# 04_ZYNQ_Config.net
KiCad netlist of a schematic drawn in Altium Designer
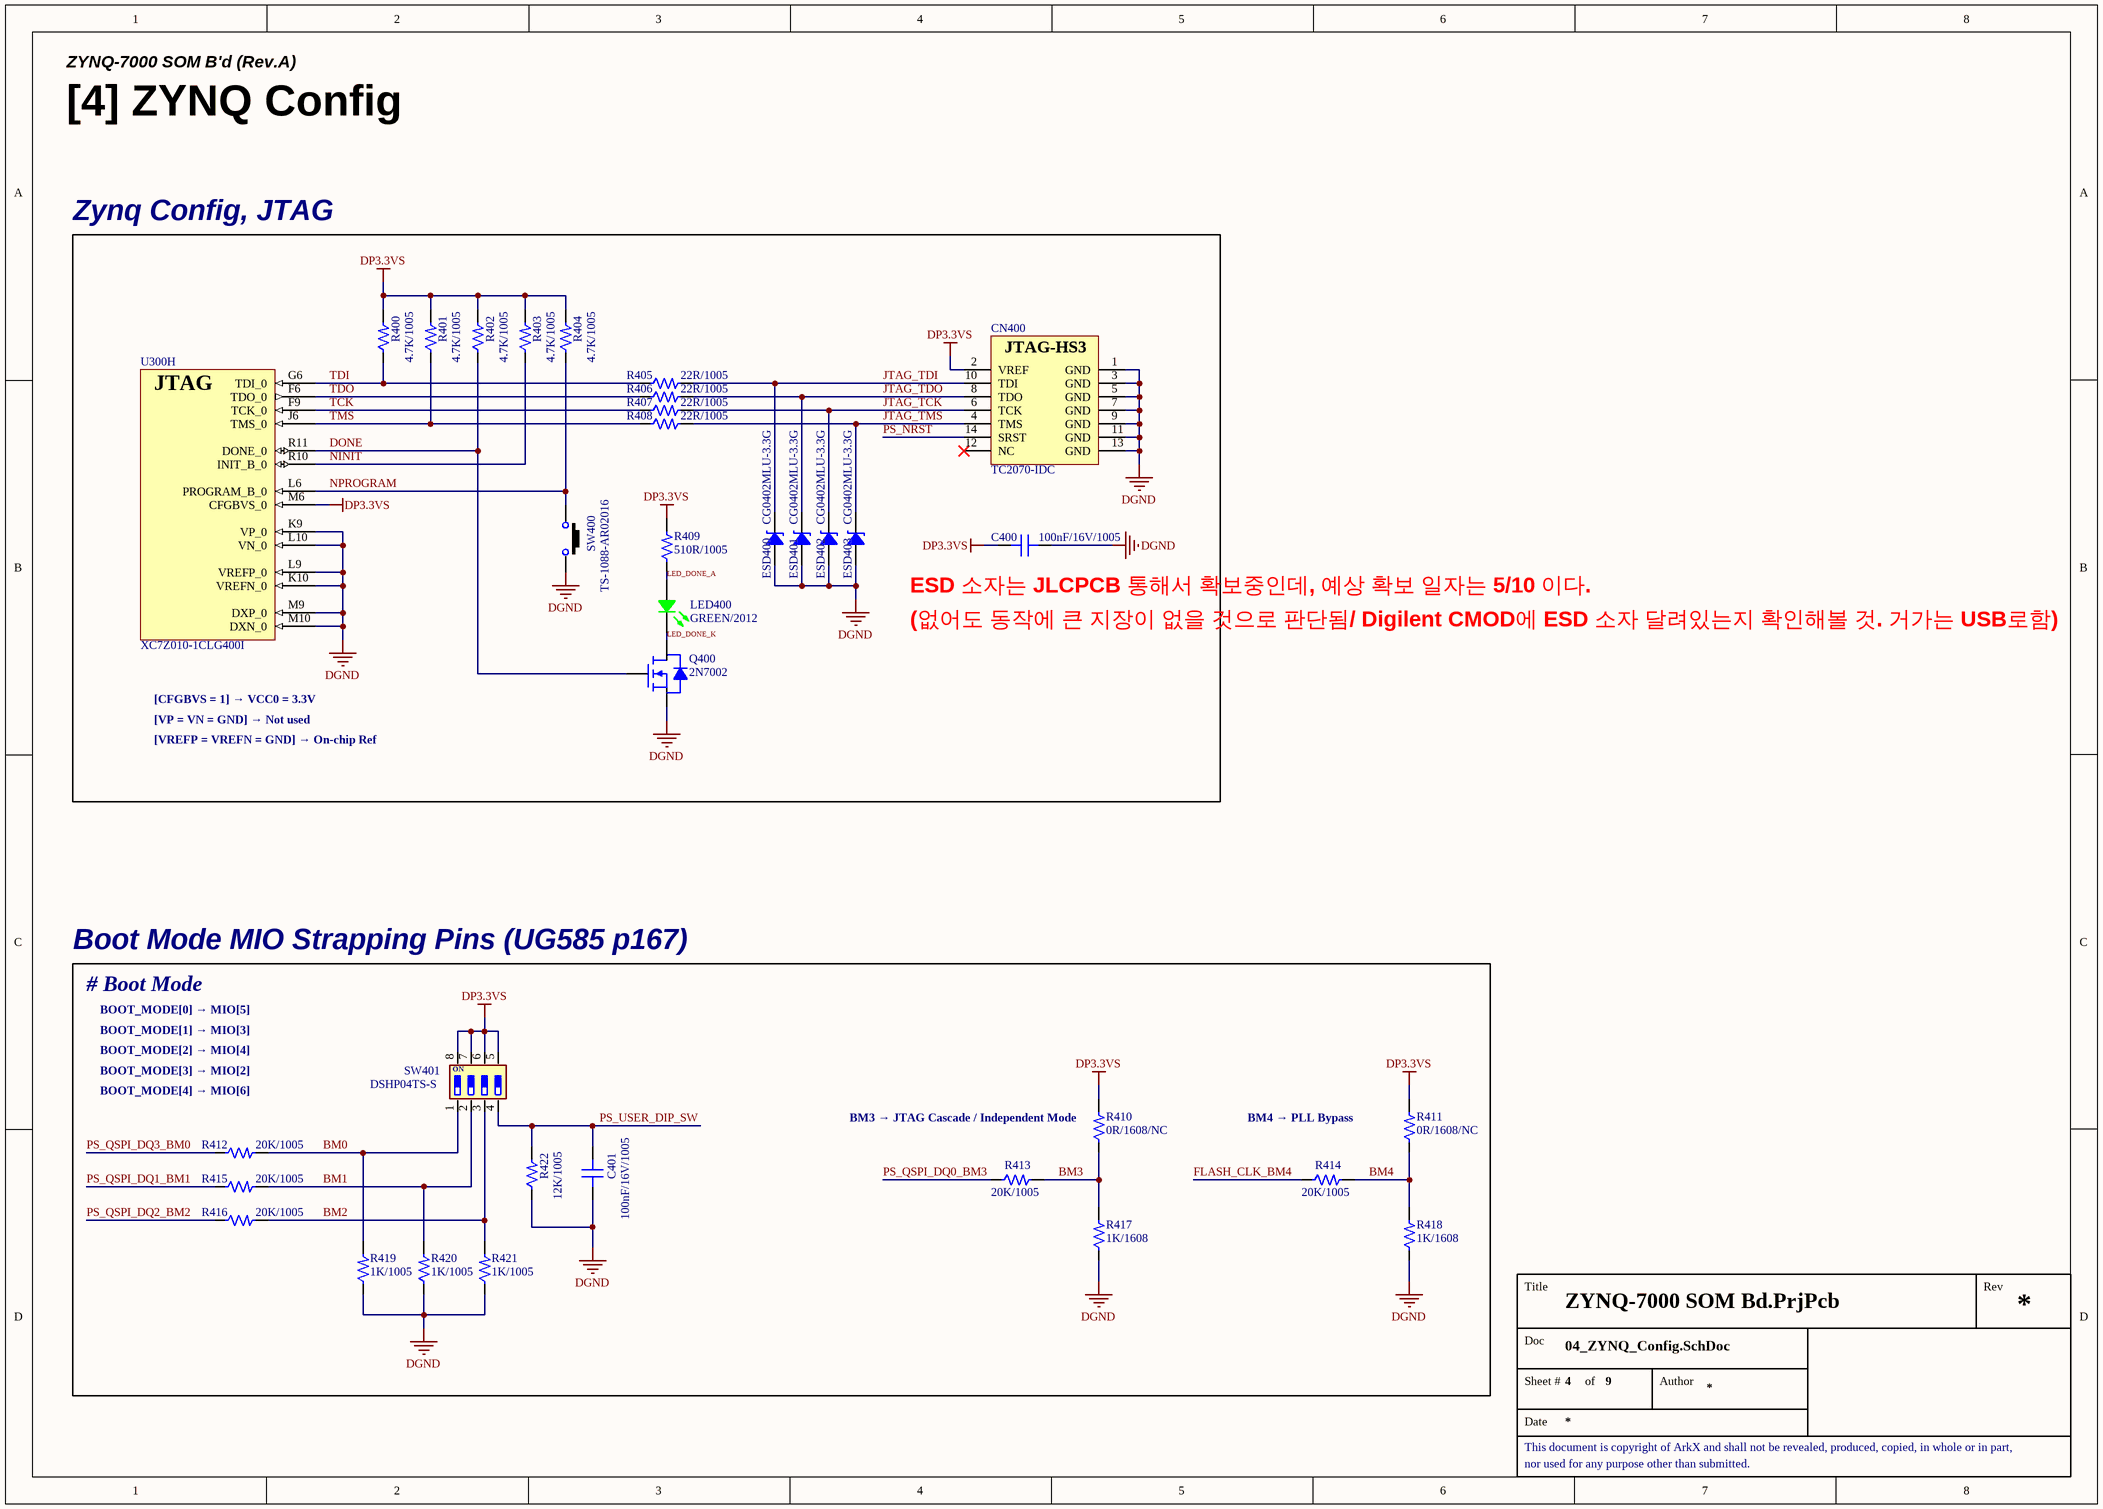
[diagram p0: 04_ZYNQ_Config.SchDoc]

(export (version "E")
  (design (tool "Eeschema 10.0.6"))
  (components
    (comp (ref "C400")
      (value "100nF/16V/1005")
      (footprint "CAP 1005 (0402_INCH)")
      (description "Ceramic CAP_100nF/16V/1005")
      (fields (field (name "LCSC PART #") "C1525"))
      (libsource (lib "Arkx") (part "CAP_100nF/16V/1005"))
    )
    (comp (ref "C401")
      (value "100nF/16V/1005")
      (footprint "CAP 1005 (0402_INCH)")
      (description "Ceramic CAP_100nF/16V/1005")
      (fields (field (name "LCSC PART #") "C1525"))
      (libsource (lib "Arkx") (part "CAP_100nF/16V/1005"))
    )
    (comp (ref "CN400")
      (value "TC2070-IDC")
      (footprint "CON_TC2070-IDC")
      (description "TC2070 14-pin Plug-of-Nails™ (with legs) to 14 pin 2mm female IDC connector.")
      (libsource (lib "Arkx") (part "CON_TC2070-IDC(JTAG-HS3)"))
    )
    (comp (ref "ESD400")
      (value "CG0402MLU-3.3G")
      (footprint "RES 1005 (0402_inch)")
      (description "Varistor 1 Circuit Surface Mount, MLCV 0402 (1005 Metric)")
      (fields (field (name "LCSC PART #") "C2655393"))
      (libsource (lib "Arkx") (part "ESD_CG0402MLU-3.3G"))
    )
    (comp (ref "ESD401")
      (value "CG0402MLU-3.3G")
      (footprint "RES 1005 (0402_inch)")
      (description "Varistor 1 Circuit Surface Mount, MLCV 0402 (1005 Metric)")
      (fields (field (name "LCSC PART #") "C2655393"))
      (libsource (lib "Arkx") (part "ESD_CG0402MLU-3.3G"))
    )
    (comp (ref "ESD402")
      (value "CG0402MLU-3.3G")
      (footprint "RES 1005 (0402_inch)")
      (description "Varistor 1 Circuit Surface Mount, MLCV 0402 (1005 Metric)")
      (fields (field (name "LCSC PART #") "C2655393"))
      (libsource (lib "Arkx") (part "ESD_CG0402MLU-3.3G"))
    )
    (comp (ref "ESD403")
      (value "CG0402MLU-3.3G")
      (footprint "RES 1005 (0402_inch)")
      (description "Varistor 1 Circuit Surface Mount, MLCV 0402 (1005 Metric)")
      (fields (field (name "LCSC PART #") "C2655393"))
      (libsource (lib "Arkx") (part "ESD_CG0402MLU-3.3G"))
    )
    (comp (ref "LED400")
      (value "GREEN/2012")
      (footprint "LED MHT170RGBCT (GREEN)")
      (fields (field (name "LCSC PART #") "C2962094"))
      (libsource (lib "Arkx") (part "LED_MHT170RGBCT(GREEN)"))
    )
    (comp (ref "Q400")
      (value "2N7002")
      (footprint "SOT 23-3 (DIODES INCORPORATED)")
      (description "60V 115mA 200mW 7.5Ω@10V,500mA N Channel SOT-23  MOSFETs ROHS")
      (fields (field (name "LCSC PART #") "C8545"))
      (libsource (lib "Arkx") (part "FET_2N7002"))
    )
    (comp (ref "R400")
      (value "4.7K/1005")
      (footprint "RES 1005 (0402_inch)")
      (description "RES_4.7K/1005/62.5mW")
      (fields (field (name "LCSC PART #") "C25900"))
      (libsource (lib "Arkx") (part "RES_4.7K/1005/62.5mW"))
    )
    (comp (ref "R401")
      (value "4.7K/1005")
      (footprint "RES 1005 (0402_inch)")
      (description "RES_4.7K/1005/62.5mW")
      (fields (field (name "LCSC PART #") "C25900"))
      (libsource (lib "Arkx") (part "RES_4.7K/1005/62.5mW"))
    )
    (comp (ref "R402")
      (value "4.7K/1005")
      (footprint "RES 1005 (0402_inch)")
      (description "RES_4.7K/1005/62.5mW")
      (fields (field (name "LCSC PART #") "C25900"))
      (libsource (lib "Arkx") (part "RES_4.7K/1005/62.5mW"))
    )
    (comp (ref "R403")
      (value "4.7K/1005")
      (footprint "RES 1005 (0402_inch)")
      (description "RES_4.7K/1005/62.5mW")
      (fields (field (name "LCSC PART #") "C25900"))
      (libsource (lib "Arkx") (part "RES_4.7K/1005/62.5mW"))
    )
    (comp (ref "R404")
      (value "4.7K/1005")
      (footprint "RES 1005 (0402_inch)")
      (description "RES_4.7K/1005/62.5mW")
      (fields (field (name "LCSC PART #") "C25900"))
      (libsource (lib "Arkx") (part "RES_4.7K/1005/62.5mW"))
    )
    (comp (ref "R405")
      (value "22R/1005")
      (footprint "RES 1005 (0402_inch)")
      (description "RES_22R/1005/62.5mW")
      (fields (field (name "LCSC PART #") "C25092"))
      (libsource (lib "Arkx") (part "RES_22R/1005/62.5mW"))
    )
    (comp (ref "R406")
      (value "22R/1005")
      (footprint "RES 1005 (0402_inch)")
      (description "RES_22R/1005/62.5mW")
      (fields (field (name "LCSC PART #") "C25092"))
      (libsource (lib "Arkx") (part "RES_22R/1005/62.5mW"))
    )
    (comp (ref "R407")
      (value "22R/1005")
      (footprint "RES 1005 (0402_inch)")
      (description "RES_22R/1005/62.5mW")
      (fields (field (name "LCSC PART #") "C25092"))
      (libsource (lib "Arkx") (part "RES_22R/1005/62.5mW"))
    )
    (comp (ref "R408")
      (value "22R/1005")
      (footprint "RES 1005 (0402_inch)")
      (description "RES_22R/1005/62.5mW")
      (fields (field (name "LCSC PART #") "C25092"))
      (libsource (lib "Arkx") (part "RES_22R/1005/62.5mW"))
    )
    (comp (ref "R409")
      (value "510R/1005")
      (footprint "RES 1005 (0402_inch)")
      (description "RES_510R/1005/62.5mW")
      (fields (field (name "LCSC PART #") "C25123"))
      (libsource (lib "Arkx") (part "RES_510R/1005/62.5mW"))
    )
    (comp (ref "R410")
      (value "0R/1608/NC")
      (footprint "RES 1608 (0603_inch)/NC")
      (description "0R/1608/0.1W/NC")
      (libsource (lib "Arkx") (part "RES_NC_0R/1608/0.1W"))
    )
    (comp (ref "R411")
      (value "0R/1608/NC")
      (footprint "RES 1608 (0603_inch)/NC")
      (description "0R/1608/0.1W/NC")
      (libsource (lib "Arkx") (part "RES_NC_0R/1608/0.1W"))
    )
    (comp (ref "R412")
      (value "20K/1005")
      (footprint "RES 1005 (0402_inch)")
      (description "RES_20K/1005/62.5mW")
      (fields (field (name "LCSC PART #") "C25765"))
      (libsource (lib "Arkx") (part "RES_20K/1005/62.5mW"))
    )
    (comp (ref "R413")
      (value "20K/1005")
      (footprint "RES 1005 (0402_inch)")
      (description "RES_20K/1005/62.5mW")
      (fields (field (name "LCSC PART #") "C25765"))
      (libsource (lib "Arkx") (part "RES_20K/1005/62.5mW"))
    )
    (comp (ref "R414")
      (value "20K/1005")
      (footprint "RES 1005 (0402_inch)")
      (description "RES_20K/1005/62.5mW")
      (fields (field (name "LCSC PART #") "C25765"))
      (libsource (lib "Arkx") (part "RES_20K/1005/62.5mW"))
    )
    (comp (ref "R415")
      (value "20K/1005")
      (footprint "RES 1005 (0402_inch)")
      (description "RES_20K/1005/62.5mW")
      (fields (field (name "LCSC PART #") "C25765"))
      (libsource (lib "Arkx") (part "RES_20K/1005/62.5mW"))
    )
    (comp (ref "R416")
      (value "20K/1005")
      (footprint "RES 1005 (0402_inch)")
      (description "RES_20K/1005/62.5mW")
      (fields (field (name "LCSC PART #") "C25765"))
      (libsource (lib "Arkx") (part "RES_20K/1005/62.5mW"))
    )
    (comp (ref "R417")
      (value "1K/1608")
      (footprint "RES 1608 (0603_inch)")
      (description "RES_1K/1608/0.1W")
      (fields (field (name "LCSC PART #") "C21190"))
      (libsource (lib "Arkx") (part "RES_1K/1608/0.1W"))
    )
    (comp (ref "R418")
      (value "1K/1608")
      (footprint "RES 1608 (0603_inch)")
      (description "RES_1K/1608/0.1W")
      (fields (field (name "LCSC PART #") "C21190"))
      (libsource (lib "Arkx") (part "RES_1K/1608/0.1W"))
    )
    (comp (ref "R419")
      (value "1K/1005")
      (footprint "RES 1005 (0402_inch)")
      (description "RES_1K/1005/62.5mW")
      (fields (field (name "LCSC PART #") "C11702"))
      (libsource (lib "Arkx") (part "RES_1K/1005/62.5mW"))
    )
    (comp (ref "R420")
      (value "1K/1005")
      (footprint "RES 1005 (0402_inch)")
      (description "RES_1K/1005/62.5mW")
      (fields (field (name "LCSC PART #") "C11702"))
      (libsource (lib "Arkx") (part "RES_1K/1005/62.5mW"))
    )
    (comp (ref "R421")
      (value "1K/1005")
      (footprint "RES 1005 (0402_inch)")
      (description "RES_1K/1005/62.5mW")
      (fields (field (name "LCSC PART #") "C11702"))
      (libsource (lib "Arkx") (part "RES_1K/1005/62.5mW"))
    )
    (comp (ref "R422")
      (value "12K/1005")
      (footprint "RES 1005 (0402_inch)")
      (description "RES_12K/1005/62.5mW")
      (fields (field (name "LCSC PART #") "C25752"))
      (libsource (lib "Arkx") (part "RES_12K/1005/62.5mW"))
    )
    (comp (ref "SW400")
      (value "TS-1088-AR02016")
      (footprint "SW_TS-1088-AR02016")
      (description "NO 50mA 100MΩ 100000 Times 12V 160gf@±50gf Brick nogging SPST SMD  Tactile Switches ROHS")
      (fields (field (name "LCSC PART #") "C720477"))
      (libsource (lib "Arkx") (part "SW_TS-1088-AR02016"))
    )
    (comp (ref "SW401")
      (value "DSHP04TS-S")
      (footprint "SW_DSHP04TS-S")
      (description "4Bit SPST 24V 25mA Black 3千次 Slide (Standard),凹槽式 SMD-8P,5.4x6.7mm  DIP Switches ROHS")
      (fields (field (name "LCSC PART #") "C319050"))
      (libsource (lib "Arkx") (part "SW_DSHP04TS-S"))
    )
    (comp (ref "U300")
      (value "XC7Z010-1CLG400I")
      (footprint "IC_SOC_XC7Z010-1CLG400I")
      (fields (field (name "LCSC PART #") "C2840994"))
      (libsource (lib "Arkx") (part "IC_SOC_XC7Z010-1CLG400I"))
    )
  )
  (nets
    (net (code "1") (name "/BM0") (class "Default")
      (node (ref "R412") (pin "2") (pinfunction "2_2") (pintype "passive"))
      (node (ref "R419") (pin "2") (pinfunction "2_2") (pintype "passive"))
      (node (ref "SW401") (pin "1") (pinfunction "1_1") (pintype "passive"))
    )
    (net (code "2") (name "/BM1") (class "Default")
      (node (ref "R415") (pin "2") (pinfunction "2_2") (pintype "passive"))
      (node (ref "R420") (pin "2") (pinfunction "2_2") (pintype "passive"))
      (node (ref "SW401") (pin "2") (pinfunction "2_2") (pintype "passive"))
    )
    (net (code "3") (name "/BM2") (class "Default")
      (node (ref "R416") (pin "2") (pinfunction "2_2") (pintype "passive"))
      (node (ref "R421") (pin "2") (pinfunction "2_2") (pintype "passive"))
      (node (ref "SW401") (pin "3") (pinfunction "3_3") (pintype "passive"))
    )
    (net (code "4") (name "/BM3") (class "Default")
      (node (ref "R410") (pin "1") (pinfunction "1_1") (pintype "passive"))
      (node (ref "R413") (pin "2") (pinfunction "2_2") (pintype "passive"))
      (node (ref "R417") (pin "2") (pinfunction "2_2") (pintype "passive"))
    )
    (net (code "5") (name "/BM4") (class "Default")
      (node (ref "R411") (pin "1") (pinfunction "1_1") (pintype "passive"))
      (node (ref "R414") (pin "2") (pinfunction "2_2") (pintype "passive"))
      (node (ref "R418") (pin "2") (pinfunction "2_2") (pintype "passive"))
    )
    (net (code "6") (name "/DONE") (class "Default")
      (node (ref "Q400") (pin "1") (pinfunction "G_1") (pintype "passive"))
      (node (ref "R402") (pin "1") (pinfunction "1_1") (pintype "passive"))
      (node (ref "U300") (pin "R11") (pinfunction "DONE_0_R11") (pintype "bidirectional"))
    )
    (net (code "7") (name "/FLASH_CLK_BM4") (class "Default")
      (node (ref "R414") (pin "1") (pinfunction "1_1") (pintype "passive"))
    )
    (net (code "8") (name "/JTAG_TCK") (class "Default")
      (node (ref "CN400") (pin "6") (pinfunction "TCK_6") (pintype "passive"))
      (node (ref "ESD402") (pin "2") (pinfunction "2_2") (pintype "passive"))
      (node (ref "R407") (pin "2") (pinfunction "2_2") (pintype "passive"))
    )
    (net (code "9") (name "/JTAG_TDI") (class "Default")
      (node (ref "CN400") (pin "10") (pinfunction "TDI_10") (pintype "passive"))
      (node (ref "ESD400") (pin "2") (pinfunction "2_2") (pintype "passive"))
      (node (ref "R405") (pin "2") (pinfunction "2_2") (pintype "passive"))
    )
    (net (code "10") (name "/JTAG_TDO") (class "Default")
      (node (ref "CN400") (pin "8") (pinfunction "TDO_8") (pintype "passive"))
      (node (ref "ESD401") (pin "2") (pinfunction "2_2") (pintype "passive"))
      (node (ref "R406") (pin "2") (pinfunction "2_2") (pintype "passive"))
    )
    (net (code "11") (name "/JTAG_TMS") (class "Default")
      (node (ref "CN400") (pin "4") (pinfunction "TMS_4") (pintype "passive"))
      (node (ref "ESD403") (pin "2") (pinfunction "2_2") (pintype "passive"))
      (node (ref "R408") (pin "2") (pinfunction "2_2") (pintype "passive"))
    )
    (net (code "12") (name "/LED_DONE_A") (class "Default")
      (node (ref "LED400") (pin "4") (pinfunction "Common_Anode_4") (pintype "passive"))
      (node (ref "R409") (pin "1") (pinfunction "1_1") (pintype "passive"))
    )
    (net (code "13") (name "/LED_DONE_K") (class "Default")
      (node (ref "LED400") (pin "2") (pinfunction "GREEN_2") (pintype "passive"))
      (node (ref "Q400") (pin "3") (pinfunction "D_3") (pintype "passive"))
    )
    (net (code "14") (name "/NINIT") (class "Default")
      (node (ref "R403") (pin "1") (pinfunction "1_1") (pintype "passive"))
      (node (ref "U300") (pin "R10") (pinfunction "INIT_B_0_R10") (pintype "bidirectional"))
    )
    (net (code "15") (name "/NPROGRAM") (class "Default")
      (node (ref "R404") (pin "1") (pinfunction "1_1") (pintype "passive"))
      (node (ref "SW400") (pin "1") (pinfunction "1_1") (pintype "passive"))
      (node (ref "U300") (pin "L6") (pinfunction "PROGRAM_B_0_L6") (pintype "input"))
    )
    (net (code "16") (name "/PS_NRST") (class "Default")
      (node (ref "CN400") (pin "14") (pinfunction "SRST_14") (pintype "passive"))
    )
    (net (code "17") (name "/PS_QSPI_DQ0_BM3") (class "Default")
      (node (ref "R413") (pin "1") (pinfunction "1_1") (pintype "passive"))
    )
    (net (code "18") (name "/PS_QSPI_DQ1_BM1") (class "Default")
      (node (ref "R415") (pin "1") (pinfunction "1_1") (pintype "passive"))
    )
    (net (code "19") (name "/PS_QSPI_DQ2_BM2") (class "Default")
      (node (ref "R416") (pin "1") (pinfunction "1_1") (pintype "passive"))
    )
    (net (code "20") (name "/PS_QSPI_DQ3_BM0") (class "Default")
      (node (ref "R412") (pin "1") (pinfunction "1_1") (pintype "passive"))
    )
    (net (code "21") (name "/PS_USER_DIP_SW") (class "Default")
      (node (ref "C401") (pin "2") (pinfunction "2_2") (pintype "passive"))
      (node (ref "R422") (pin "2") (pinfunction "2_2") (pintype "passive"))
      (node (ref "SW401") (pin "4") (pinfunction "4_4") (pintype "passive"))
    )
    (net (code "22") (name "/TCK") (class "Default")
      (node (ref "R407") (pin "1") (pinfunction "1_1") (pintype "passive"))
      (node (ref "U300") (pin "F9") (pinfunction "TCK_0_F9") (pintype "input"))
    )
    (net (code "23") (name "/TDI") (class "Default")
      (node (ref "R400") (pin "1") (pinfunction "1_1") (pintype "passive"))
      (node (ref "R405") (pin "1") (pinfunction "1_1") (pintype "passive"))
      (node (ref "U300") (pin "G6") (pinfunction "TDI_0_G6") (pintype "input"))
    )
    (net (code "24") (name "/TDO") (class "Default")
      (node (ref "R406") (pin "1") (pinfunction "1_1") (pintype "passive"))
      (node (ref "U300") (pin "F6") (pinfunction "TDO_0_F6") (pintype "output"))
    )
    (net (code "25") (name "/TMS") (class "Default")
      (node (ref "R401") (pin "1") (pinfunction "1_1") (pintype "passive"))
      (node (ref "R408") (pin "1") (pinfunction "1_1") (pintype "passive"))
      (node (ref "U300") (pin "J6") (pinfunction "TMS_0_J6") (pintype "input"))
    )
    (net (code "26") (name "DGND") (class "Default")
      (node (ref "C400") (pin "1") (pinfunction "1_1") (pintype "passive"))
      (node (ref "C401") (pin "1") (pinfunction "1_1") (pintype "passive"))
      (node (ref "CN400") (pin "1") (pinfunction "GND_1") (pintype "passive"))
      (node (ref "CN400") (pin "11") (pinfunction "GND_11") (pintype "passive"))
      (node (ref "CN400") (pin "13") (pinfunction "GND_13") (pintype "passive"))
      (node (ref "CN400") (pin "3") (pinfunction "GND_3") (pintype "passive"))
      (node (ref "CN400") (pin "5") (pinfunction "GND_5") (pintype "passive"))
      (node (ref "CN400") (pin "7") (pinfunction "GND_7") (pintype "passive"))
      (node (ref "CN400") (pin "9") (pinfunction "GND_9") (pintype "passive"))
      (node (ref "ESD400") (pin "1") (pinfunction "1_1") (pintype "passive"))
      (node (ref "ESD401") (pin "1") (pinfunction "1_1") (pintype "passive"))
      (node (ref "ESD402") (pin "1") (pinfunction "1_1") (pintype "passive"))
      (node (ref "ESD403") (pin "1") (pinfunction "1_1") (pintype "passive"))
      (node (ref "Q400") (pin "2") (pinfunction "S_2") (pintype "passive"))
      (node (ref "R417") (pin "1") (pinfunction "1_1") (pintype "passive"))
      (node (ref "R418") (pin "1") (pinfunction "1_1") (pintype "passive"))
      (node (ref "R419") (pin "1") (pinfunction "1_1") (pintype "passive"))
      (node (ref "R420") (pin "1") (pinfunction "1_1") (pintype "passive"))
      (node (ref "R421") (pin "1") (pinfunction "1_1") (pintype "passive"))
      (node (ref "R422") (pin "1") (pinfunction "1_1") (pintype "passive"))
      (node (ref "SW400") (pin "2") (pinfunction "2_2") (pintype "passive"))
      (node (ref "U300") (pin "K10") (pinfunction "VREFN_0_K10") (pintype "input"))
      (node (ref "U300") (pin "K9") (pinfunction "VP_0_K9") (pintype "input"))
      (node (ref "U300") (pin "L10") (pinfunction "VN_0_L10") (pintype "input"))
      (node (ref "U300") (pin "L9") (pinfunction "VREFP_0_L9") (pintype "input"))
      (node (ref "U300") (pin "M10") (pinfunction "DXN_0_M10") (pintype "input"))
      (node (ref "U300") (pin "M9") (pinfunction "DXP_0_M9") (pintype "input"))
    )
    (net (code "27") (name "DP3.3VS") (class "Default")
      (node (ref "C400") (pin "2") (pinfunction "2_2") (pintype "passive"))
      (node (ref "CN400") (pin "2") (pinfunction "VREF_2") (pintype "passive"))
      (node (ref "R400") (pin "2") (pinfunction "2_2") (pintype "passive"))
      (node (ref "R401") (pin "2") (pinfunction "2_2") (pintype "passive"))
      (node (ref "R402") (pin "2") (pinfunction "2_2") (pintype "passive"))
      (node (ref "R403") (pin "2") (pinfunction "2_2") (pintype "passive"))
      (node (ref "R404") (pin "2") (pinfunction "2_2") (pintype "passive"))
      (node (ref "R409") (pin "2") (pinfunction "2_2") (pintype "passive"))
      (node (ref "R410") (pin "2") (pinfunction "2_2") (pintype "passive"))
      (node (ref "R411") (pin "2") (pinfunction "2_2") (pintype "passive"))
      (node (ref "SW401") (pin "5") (pinfunction "5_5") (pintype "passive"))
      (node (ref "SW401") (pin "6") (pinfunction "6_6") (pintype "passive"))
      (node (ref "SW401") (pin "7") (pinfunction "7_7") (pintype "passive"))
      (node (ref "SW401") (pin "8") (pinfunction "8_8") (pintype "passive"))
      (node (ref "U300") (pin "M6") (pinfunction "CFGBVS_0_M6") (pintype "input"))
    )
    (net (code "28") (name "unconnected-(CN400-NC-Pad12)") (class "Default")
      (node (ref "CN400") (pin "12") (pinfunction "NC_12") (pintype "passive+no_connect"))
    )
  )
)
